# Interface.net
KiCad netlist of a schematic drawn in Altium Designer
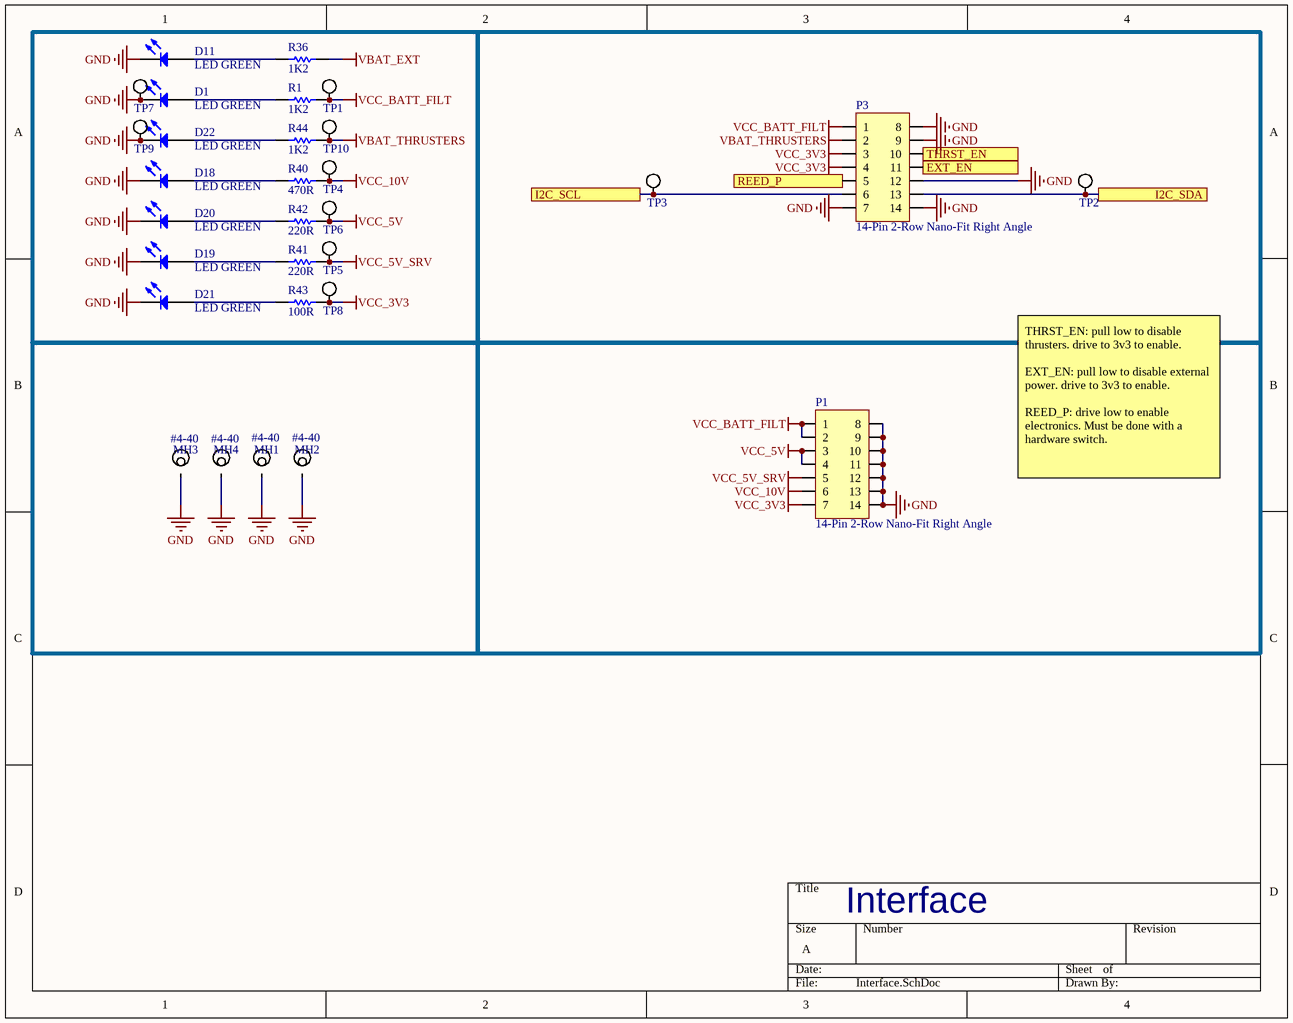
[diagram p0: Interface.SchDoc]

(export (version "E")
  (design (tool "Eeschema 10.0.6"))
  (components
    (comp (ref "D1")
      (value "LED GREEN")
      (footprint "LED_0805")
      (description "led")
      (fields
        (field (name "MANUFACTURER") "Lite-On Inc.")
        (field (name "MANUFACTURER PART NUMBER") "LTST-C171KGKT")
      )
      (libsource (lib "CMR_Miscellaneous_Devices") (part "LED0"))
    )
    (comp (ref "D11")
      (value "LED GREEN")
      (footprint "LED_0805")
      (description "led")
      (fields
        (field (name "MANUFACTURER") "Lite-On Inc.")
        (field (name "MANUFACTURER PART NUMBER") "LTST-C171KGKT")
      )
      (libsource (lib "CMR_Miscellaneous_Devices") (part "LED0"))
    )
    (comp (ref "D18")
      (value "LED GREEN")
      (footprint "LED_0805")
      (description "led")
      (fields
        (field (name "MANUFACTURER") "Lite-On Inc.")
        (field (name "MANUFACTURER PART NUMBER") "LTST-C171KGKT")
      )
      (libsource (lib "CMR_Miscellaneous_Devices") (part "LED0"))
    )
    (comp (ref "D19")
      (value "LED GREEN")
      (footprint "LED_0805")
      (description "led")
      (fields
        (field (name "MANUFACTURER") "Lite-On Inc.")
        (field (name "MANUFACTURER PART NUMBER") "LTST-C171KGKT")
      )
      (libsource (lib "CMR_Miscellaneous_Devices") (part "LED0"))
    )
    (comp (ref "D20")
      (value "LED GREEN")
      (footprint "LED_0805")
      (description "led")
      (fields
        (field (name "MANUFACTURER") "Lite-On Inc.")
        (field (name "MANUFACTURER PART NUMBER") "LTST-C171KGKT")
      )
      (libsource (lib "CMR_Miscellaneous_Devices") (part "LED0"))
    )
    (comp (ref "D21")
      (value "LED GREEN")
      (footprint "LED_0805")
      (description "led")
      (fields
        (field (name "MANUFACTURER") "Lite-On Inc.")
        (field (name "MANUFACTURER PART NUMBER") "LTST-C171KGKT")
      )
      (libsource (lib "CMR_Miscellaneous_Devices") (part "LED0"))
    )
    (comp (ref "D22")
      (value "LED GREEN")
      (footprint "LED_0805")
      (description "led")
      (fields
        (field (name "MANUFACTURER") "Lite-On Inc.")
        (field (name "MANUFACTURER PART NUMBER") "LTST-C171KGKT")
      )
      (libsource (lib "CMR_Miscellaneous_Devices") (part "LED0"))
    )
    (comp (ref "MH1")
      (value "#4-40")
      (footprint "Mounting Hole #4-40")
      (description "Mounting Hole for ANSI #4-40 w/ Flat Washer, Loose Fit")
      (libsource (lib "CMR_PCB_Components") (part "Mounting Hole #4-40, Loose Fit"))
    )
    (comp (ref "MH2")
      (value "#4-40")
      (footprint "Mounting Hole #4-40")
      (description "Mounting Hole for ANSI #4-40 w/ Flat Washer, Loose Fit")
      (libsource (lib "CMR_PCB_Components") (part "Mounting Hole #4-40, Loose Fit"))
    )
    (comp (ref "MH3")
      (value "#4-40")
      (footprint "Mounting Hole #4-40")
      (description "Mounting Hole for ANSI #4-40 w/ Flat Washer, Loose Fit")
      (libsource (lib "CMR_PCB_Components") (part "Mounting Hole #4-40, Loose Fit"))
    )
    (comp (ref "MH4")
      (value "#4-40")
      (footprint "Mounting Hole #4-40")
      (description "Mounting Hole for ANSI #4-40 w/ Flat Washer, Loose Fit")
      (libsource (lib "CMR_PCB_Components") (part "Mounting Hole #4-40, Loose Fit"))
    )
    (comp (ref "P1")
      (value "14-Pin 2-Row Nano-Fit Right Angle")
      (footprint "MOLEX NANO-FIT 2X7 - Right Angle")
      (description "NanoFit Right Hdr TH DR 14Ckt")
      (fields (field (name "PART NUMBER") "105314-1214") (field (name "MANUFACTURER") "Molex"))
      (libsource (lib "CMR_Connectors") (part "14-Pin 2-Row Nano-Fit Right Angle"))
    )
    (comp (ref "P3")
      (value "14-Pin 2-Row Nano-Fit Right Angle")
      (footprint "MOLEX NANO-FIT 2X7 - Right Angle")
      (description "NanoFit Right Hdr TH DR 14Ckt")
      (fields (field (name "PART NUMBER") "105314-1214") (field (name "MANUFACTURER") "Molex"))
      (libsource (lib "CMR_Connectors") (part "14-Pin 2-Row Nano-Fit Right Angle"))
    )
    (comp (ref "R1")
      (value "1K2")
      (footprint "RESC0603(1608)_L")
      (description "1K2 0.1W 1% 0603 (1608 Metric)  SMD")
      (fields (field (name "POWER") "0.1 W") (field (name "TOLERANCE") "1 %"))
      (libsource (lib "Altium Content Vault") (part "RES"))
    )
    (comp (ref "R36")
      (value "1K2")
      (footprint "RESC0603(1608)_L")
      (description "1K2 0.1W 1% 0603 (1608 Metric)  SMD")
      (fields (field (name "POWER") "0.1 W") (field (name "TOLERANCE") "1 %"))
      (libsource (lib "Altium Content Vault") (part "RES"))
    )
    (comp (ref "R40")
      (value "470R")
      (footprint "RESC0603(1608)_L")
      (description "470R 0.1W 1% 0603 (1608 Metric)  SMD")
      (fields (field (name "POWER") "0.1 W") (field (name "TOLERANCE") "1 %"))
      (libsource (lib "Altium Content Vault") (part "RES"))
    )
    (comp (ref "R41")
      (value "220R")
      (footprint "RESC0603(1608)_L")
      (description "220R 0.1W 5% 0603 (1608 Metric)  SMD")
      (fields (field (name "POWER") "0.1 W") (field (name "TOLERANCE") "5 %"))
      (libsource (lib "Altium Content Vault") (part "RES"))
    )
    (comp (ref "R42")
      (value "220R")
      (footprint "RESC0603(1608)_L")
      (description "220R 0.1W 5% 0603 (1608 Metric)  SMD")
      (fields (field (name "POWER") "0.1 W") (field (name "TOLERANCE") "5 %"))
      (libsource (lib "Altium Content Vault") (part "RES"))
    )
    (comp (ref "R43")
      (value "100R")
      (footprint "RESC0603(1608)_L")
      (description "100R 0.1W 5% 0603 (1608 Metric)  SMD")
      (fields (field (name "TOLERANCE") "5 %") (field (name "POWER") "0.1 W"))
      (libsource (lib "Altium Content Vault") (part "RES"))
    )
    (comp (ref "R44")
      (value "1K2")
      (footprint "RESC0603(1608)_L")
      (description "1K2 0.1W 1% 0603 (1608 Metric)  SMD")
      (fields (field (name "POWER") "0.1 W") (field (name "TOLERANCE") "1 %"))
      (libsource (lib "Altium Content Vault") (part "RES"))
    )
    (comp (ref "TP1")
      (value "Test Point Loop")
      (footprint "Test Point Loop - Black")
      (description "Keyston Electronics 5001 Test Point Loop")
      (fields (field (name "MANUFACTURER") "Keystone Electronics"))
      (libsource (lib "CMR_PCB_Components") (part "Test Point Loop"))
    )
    (comp (ref "TP2")
      (value "Test Point Loop")
      (footprint "Test Point Loop - Black")
      (description "Keyston Electronics 5001 Test Point Loop")
      (fields (field (name "MANUFACTURER") "Keystone Electronics"))
      (libsource (lib "CMR_PCB_Components") (part "Test Point Loop"))
    )
    (comp (ref "TP3")
      (value "Test Point Loop")
      (footprint "Test Point Loop - Black")
      (description "Keyston Electronics 5001 Test Point Loop")
      (fields (field (name "MANUFACTURER") "Keystone Electronics"))
      (libsource (lib "CMR_PCB_Components") (part "Test Point Loop"))
    )
    (comp (ref "TP4")
      (value "Test Point Loop")
      (footprint "Test Point Loop - Black")
      (description "Keyston Electronics 5001 Test Point Loop")
      (fields (field (name "MANUFACTURER") "Keystone Electronics"))
      (libsource (lib "CMR_PCB_Components") (part "Test Point Loop"))
    )
    (comp (ref "TP5")
      (value "Test Point Loop")
      (footprint "Test Point Loop - Black")
      (description "Keyston Electronics 5001 Test Point Loop")
      (fields (field (name "MANUFACTURER") "Keystone Electronics"))
      (libsource (lib "CMR_PCB_Components") (part "Test Point Loop"))
    )
    (comp (ref "TP6")
      (value "Test Point Loop")
      (footprint "Test Point Loop - Black")
      (description "Keyston Electronics 5001 Test Point Loop")
      (fields (field (name "MANUFACTURER") "Keystone Electronics"))
      (libsource (lib "CMR_PCB_Components") (part "Test Point Loop"))
    )
    (comp (ref "TP7")
      (value "Test Point Loop")
      (footprint "Test Point Loop - Black")
      (description "Keyston Electronics 5001 Test Point Loop")
      (fields (field (name "MANUFACTURER") "Keystone Electronics"))
      (libsource (lib "CMR_PCB_Components") (part "Test Point Loop"))
    )
    (comp (ref "TP8")
      (value "Test Point Loop")
      (footprint "Test Point Loop - Black")
      (description "Keyston Electronics 5001 Test Point Loop")
      (fields (field (name "MANUFACTURER") "Keystone Electronics"))
      (libsource (lib "CMR_PCB_Components") (part "Test Point Loop"))
    )
    (comp (ref "TP9")
      (value "Test Point Loop")
      (footprint "Test Point Loop - Black")
      (description "Keyston Electronics 5001 Test Point Loop")
      (fields (field (name "MANUFACTURER") "Keystone Electronics"))
      (libsource (lib "CMR_PCB_Components") (part "Test Point Loop"))
    )
    (comp (ref "TP10")
      (value "Test Point Loop")
      (footprint "Test Point Loop - Black")
      (description "Keyston Electronics 5001 Test Point Loop")
      (fields (field (name "MANUFACTURER") "Keystone Electronics"))
      (libsource (lib "CMR_PCB_Components") (part "Test Point Loop"))
    )
  )
  (nets
    (net (code "1") (name "/EXT_EN") (class "Default")
      (node (ref "P3") (pin "11") (pinfunction "11_11") (pintype "passive"))
    )
    (net (code "2") (name "/I2C_SCL") (class "Default")
      (node (ref "P3") (pin "6") (pinfunction "6_6") (pintype "passive"))
      (node (ref "TP3") (pin "1") (pinfunction "1_1") (pintype "passive"))
    )
    (net (code "3") (name "/I2C_SDA") (class "Default")
      (node (ref "P3") (pin "13") (pinfunction "13_13") (pintype "passive"))
      (node (ref "TP2") (pin "1") (pinfunction "1_1") (pintype "passive"))
    )
    (net (code "4") (name "/REED_P") (class "Default")
      (node (ref "P3") (pin "5") (pinfunction "5_5") (pintype "passive"))
    )
    (net (code "5") (name "/THRST_EN") (class "Default")
      (node (ref "P3") (pin "10") (pinfunction "10_10") (pintype "passive"))
    )
    (net (code "6") (name "GND") (class "Default")
      (node (ref "D1") (pin "1") (pinfunction "K_1") (pintype "passive"))
      (node (ref "D11") (pin "1") (pinfunction "K_1") (pintype "passive"))
      (node (ref "D18") (pin "1") (pinfunction "K_1") (pintype "passive"))
      (node (ref "D19") (pin "1") (pinfunction "K_1") (pintype "passive"))
      (node (ref "D20") (pin "1") (pinfunction "K_1") (pintype "passive"))
      (node (ref "D21") (pin "1") (pinfunction "K_1") (pintype "passive"))
      (node (ref "D22") (pin "1") (pinfunction "K_1") (pintype "passive"))
      (node (ref "MH1") (pin "0") (pinfunction "0_0") (pintype "passive"))
      (node (ref "MH2") (pin "0") (pinfunction "0_0") (pintype "passive"))
      (node (ref "MH3") (pin "0") (pinfunction "0_0") (pintype "passive"))
      (node (ref "MH4") (pin "0") (pinfunction "0_0") (pintype "passive"))
      (node (ref "P1") (pin "10") (pinfunction "10_10") (pintype "passive"))
      (node (ref "P1") (pin "11") (pinfunction "11_11") (pintype "passive"))
      (node (ref "P1") (pin "12") (pinfunction "12_12") (pintype "passive"))
      (node (ref "P1") (pin "13") (pinfunction "13_13") (pintype "passive"))
      (node (ref "P1") (pin "14") (pinfunction "14_14") (pintype "passive"))
      (node (ref "P1") (pin "8") (pinfunction "8_8") (pintype "passive"))
      (node (ref "P1") (pin "9") (pinfunction "9_9") (pintype "passive"))
      (node (ref "P3") (pin "12") (pinfunction "12_12") (pintype "passive"))
      (node (ref "P3") (pin "14") (pinfunction "14_14") (pintype "passive"))
      (node (ref "P3") (pin "7") (pinfunction "7_7") (pintype "passive"))
      (node (ref "P3") (pin "8") (pinfunction "8_8") (pintype "passive"))
      (node (ref "P3") (pin "9") (pinfunction "9_9") (pintype "passive"))
      (node (ref "TP7") (pin "1") (pinfunction "1_1") (pintype "passive"))
      (node (ref "TP9") (pin "1") (pinfunction "1_1") (pintype "passive"))
    )
    (net (code "7") (name "Net-(D1-A)") (class "Default")
      (node (ref "D1") (pin "2") (pinfunction "A_2") (pintype "passive"))
      (node (ref "R1") (pin "1") (pinfunction "1_1") (pintype "passive"))
    )
    (net (code "8") (name "Net-(D11-A)") (class "Default")
      (node (ref "D11") (pin "2") (pinfunction "A_2") (pintype "passive"))
      (node (ref "R36") (pin "1") (pinfunction "1_1") (pintype "passive"))
    )
    (net (code "9") (name "Net-(D18-A)") (class "Default")
      (node (ref "D18") (pin "2") (pinfunction "A_2") (pintype "passive"))
      (node (ref "R40") (pin "1") (pinfunction "1_1") (pintype "passive"))
    )
    (net (code "10") (name "Net-(D19-A)") (class "Default")
      (node (ref "D19") (pin "2") (pinfunction "A_2") (pintype "passive"))
      (node (ref "R41") (pin "1") (pinfunction "1_1") (pintype "passive"))
    )
    (net (code "11") (name "Net-(D20-A)") (class "Default")
      (node (ref "D20") (pin "2") (pinfunction "A_2") (pintype "passive"))
      (node (ref "R42") (pin "1") (pinfunction "1_1") (pintype "passive"))
    )
    (net (code "12") (name "Net-(D21-A)") (class "Default")
      (node (ref "D21") (pin "2") (pinfunction "A_2") (pintype "passive"))
      (node (ref "R43") (pin "1") (pinfunction "1_1") (pintype "passive"))
    )
    (net (code "13") (name "Net-(D22-A)") (class "Default")
      (node (ref "D22") (pin "2") (pinfunction "A_2") (pintype "passive"))
      (node (ref "R44") (pin "1") (pinfunction "1_1") (pintype "passive"))
    )
    (net (code "14") (name "VBAT_EXT") (class "Default")
      (node (ref "R36") (pin "2") (pinfunction "2_2") (pintype "passive"))
    )
    (net (code "15") (name "VBAT_THRUSTERS") (class "Default")
      (node (ref "P3") (pin "2") (pinfunction "2_2") (pintype "passive"))
      (node (ref "R44") (pin "2") (pinfunction "2_2") (pintype "passive"))
      (node (ref "TP10") (pin "1") (pinfunction "1_1") (pintype "passive"))
    )
    (net (code "16") (name "VCC_3V3") (class "Default")
      (node (ref "P1") (pin "7") (pinfunction "7_7") (pintype "passive"))
      (node (ref "P3") (pin "3") (pinfunction "3_3") (pintype "passive"))
      (node (ref "P3") (pin "4") (pinfunction "4_4") (pintype "passive"))
      (node (ref "R43") (pin "2") (pinfunction "2_2") (pintype "passive"))
      (node (ref "TP8") (pin "1") (pinfunction "1_1") (pintype "passive"))
    )
    (net (code "17") (name "VCC_5V") (class "Default")
      (node (ref "P1") (pin "3") (pinfunction "3_3") (pintype "passive"))
      (node (ref "P1") (pin "4") (pinfunction "4_4") (pintype "passive"))
      (node (ref "R42") (pin "2") (pinfunction "2_2") (pintype "passive"))
      (node (ref "TP6") (pin "1") (pinfunction "1_1") (pintype "passive"))
    )
    (net (code "18") (name "VCC_5V_SRV") (class "Default")
      (node (ref "P1") (pin "5") (pinfunction "5_5") (pintype "passive"))
      (node (ref "R41") (pin "2") (pinfunction "2_2") (pintype "passive"))
      (node (ref "TP5") (pin "1") (pinfunction "1_1") (pintype "passive"))
    )
    (net (code "19") (name "VCC_10V") (class "Default")
      (node (ref "P1") (pin "6") (pinfunction "6_6") (pintype "passive"))
      (node (ref "R40") (pin "2") (pinfunction "2_2") (pintype "passive"))
      (node (ref "TP4") (pin "1") (pinfunction "1_1") (pintype "passive"))
    )
    (net (code "20") (name "VCC_BATT_FILT") (class "Default")
      (node (ref "P1") (pin "1") (pinfunction "1_1") (pintype "passive"))
      (node (ref "P1") (pin "2") (pinfunction "2_2") (pintype "passive"))
      (node (ref "P3") (pin "1") (pinfunction "1_1") (pintype "passive"))
      (node (ref "R1") (pin "2") (pinfunction "2_2") (pintype "passive"))
      (node (ref "TP1") (pin "1") (pinfunction "1_1") (pintype "passive"))
    )
  )
)
